# xlr_headphone_amp.net
KiCad netlist of a schematic drawn in EAGLE
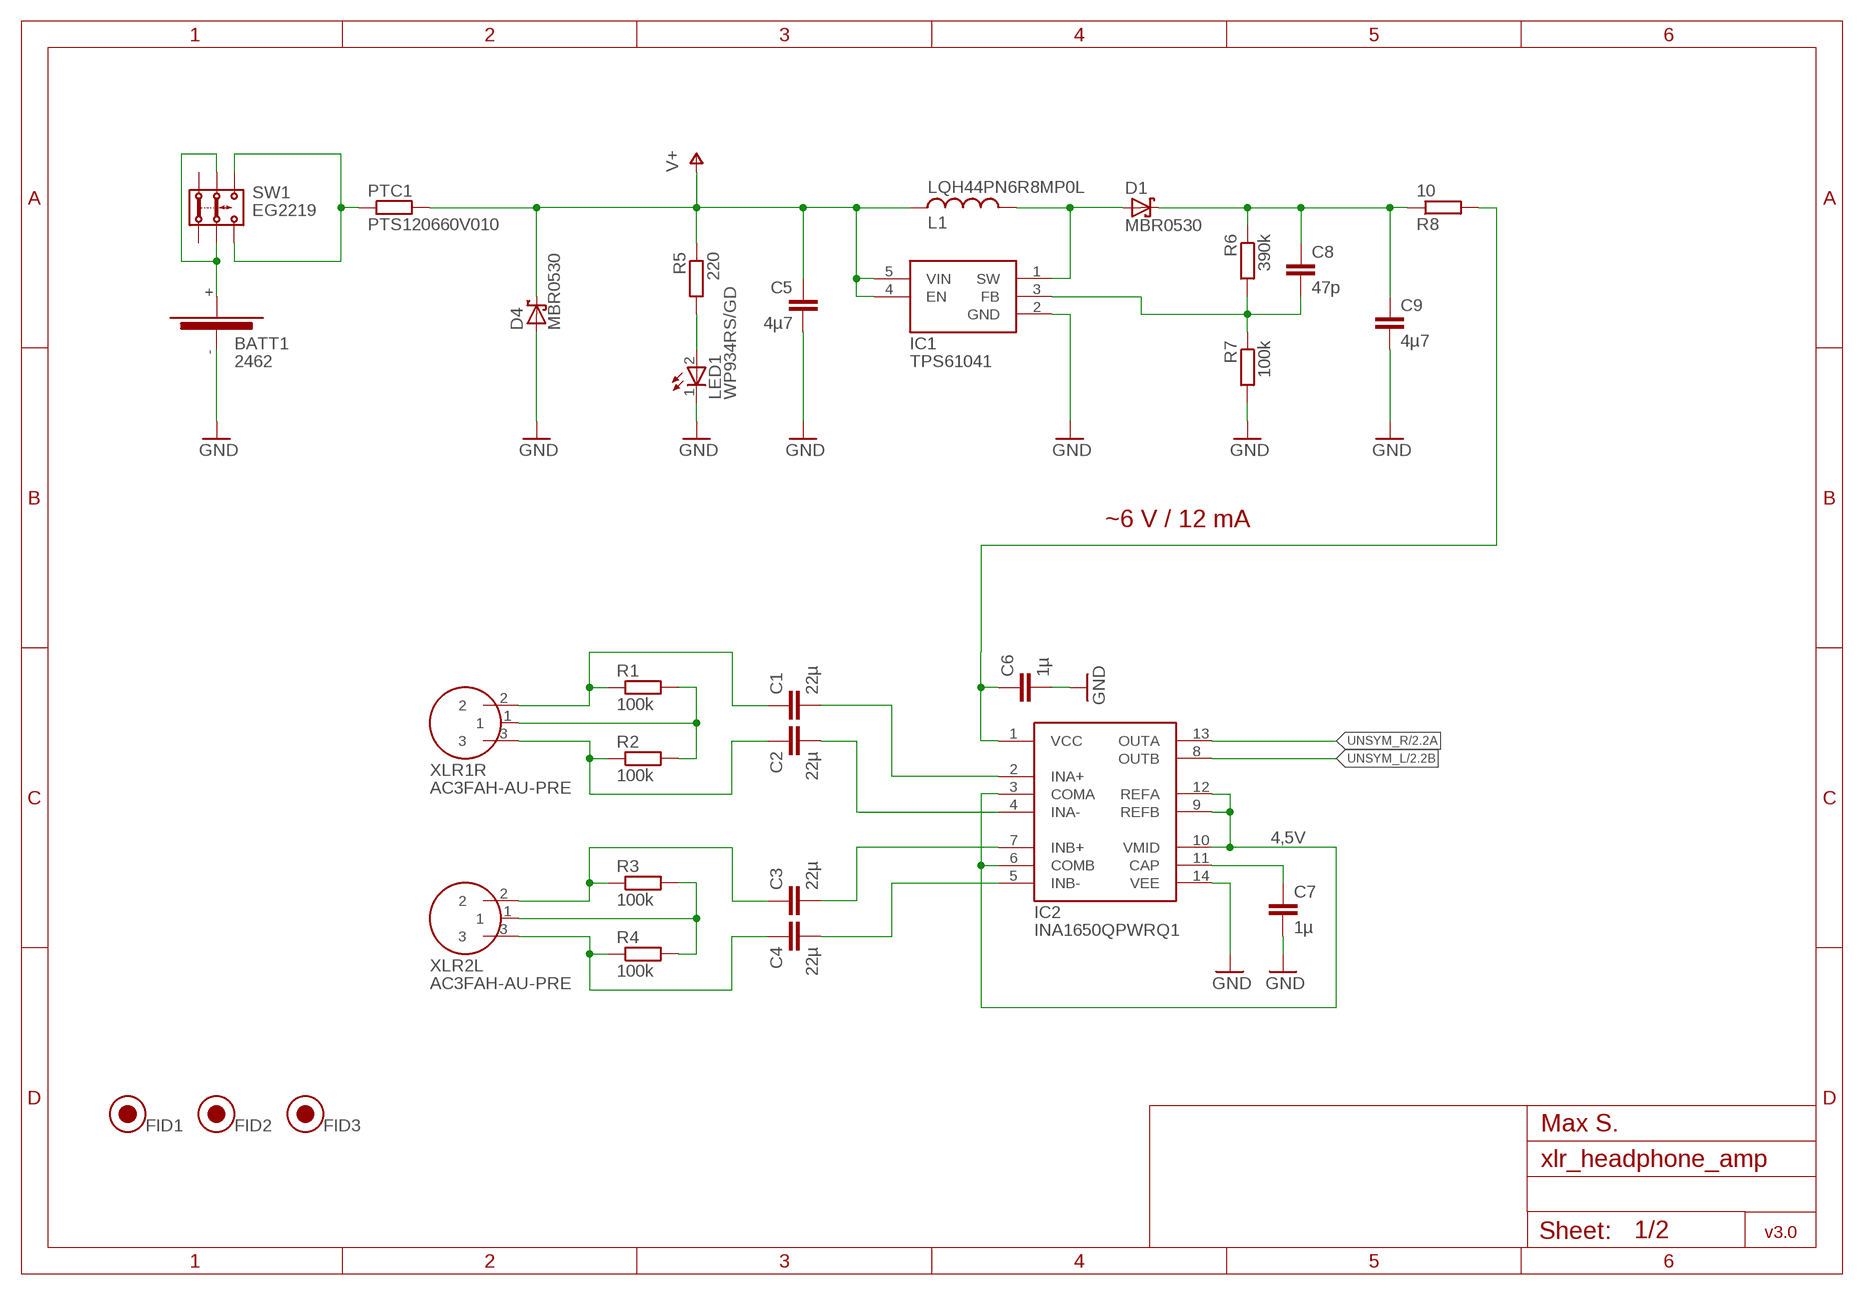
[diagram p0: schematic, sheet 1]
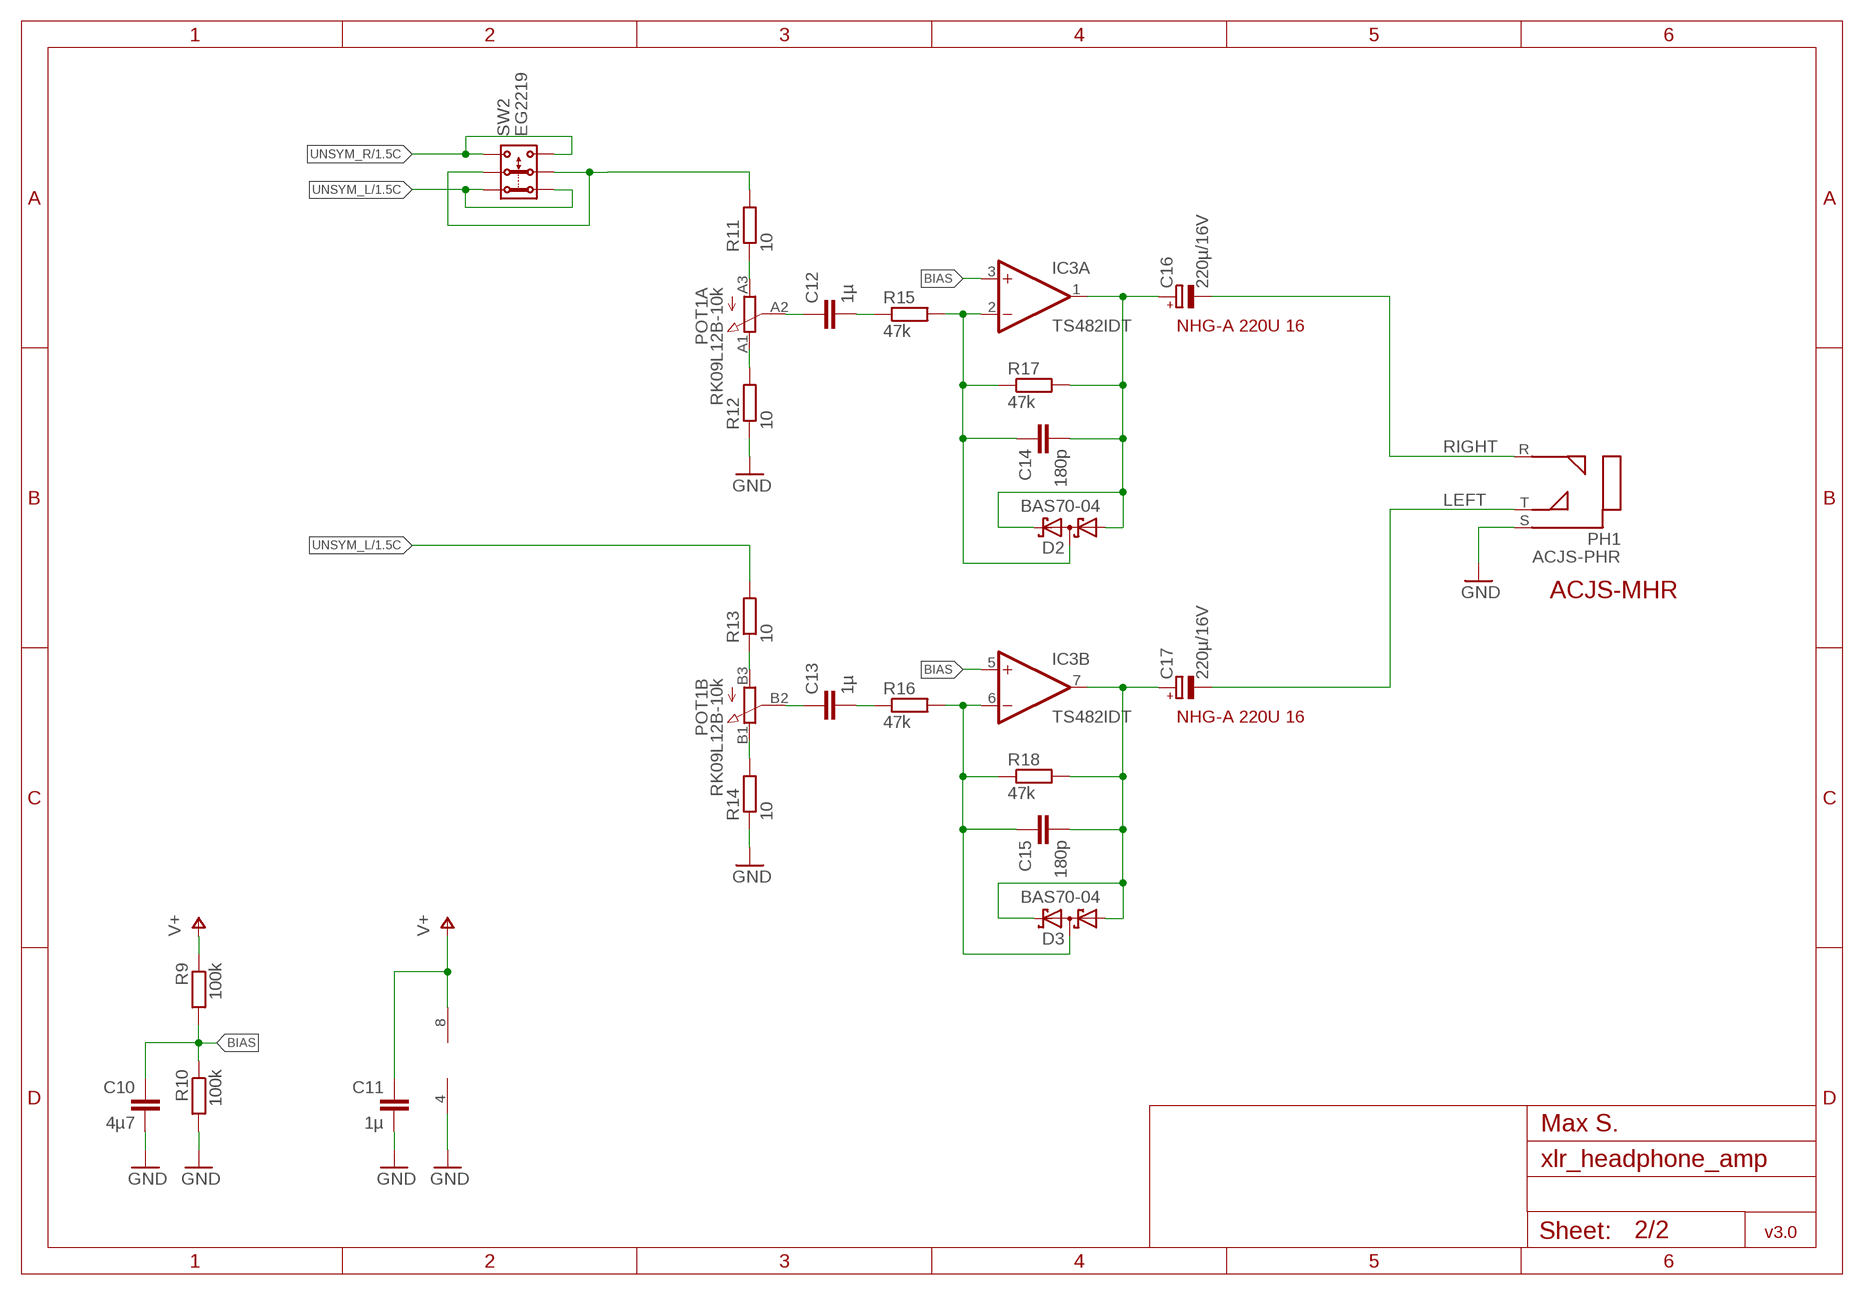
[diagram p1: schematic, sheet 2]

(export (version "E")
  (design (tool "Eeschema 10.0.6"))
  (components
    (comp (ref "BATT1")
      (value "2462")
      (footprint "eagle-import:2462")
      (libsource (lib "eagle-import") (part "BATT_HOLDERBATT"))
    )
    (comp (ref "C1")
      (value "22µ")
      (footprint "eagle-import:C1206")
      (libsource (lib "eagle-import") (part "C_EU1206"))
    )
    (comp (ref "C2")
      (value "22µ")
      (footprint "eagle-import:C1206")
      (libsource (lib "eagle-import") (part "C_EU1206"))
    )
    (comp (ref "C3")
      (value "22µ")
      (footprint "eagle-import:C1206")
      (libsource (lib "eagle-import") (part "C_EU1206"))
    )
    (comp (ref "C4")
      (value "22µ")
      (footprint "eagle-import:C1206")
      (libsource (lib "eagle-import") (part "C_EU1206"))
    )
    (comp (ref "C5")
      (value "4µ7")
      (footprint "eagle-import:C1206")
      (libsource (lib "eagle-import") (part "C_EU1206"))
    )
    (comp (ref "C6")
      (value "1µ")
      (footprint "eagle-import:C1206")
      (libsource (lib "eagle-import") (part "C_EU1206"))
    )
    (comp (ref "C7")
      (value "1µ")
      (footprint "eagle-import:C1206")
      (libsource (lib "eagle-import") (part "C_EU1206"))
    )
    (comp (ref "C8")
      (value "47p")
      (footprint "eagle-import:C1206")
      (libsource (lib "eagle-import") (part "C_EU1206"))
    )
    (comp (ref "C9")
      (value "4µ7")
      (footprint "eagle-import:C1206")
      (libsource (lib "eagle-import") (part "C_EU1206"))
    )
    (comp (ref "D1")
      (value "MBR0530")
      (footprint "eagle-import:SOD123")
      (libsource (lib "eagle-import") (part "SCHOTTKY-DIODESOD123"))
    )
    (comp (ref "D4")
      (value "MBR0530")
      (footprint "eagle-import:SOD123")
      (libsource (lib "eagle-import") (part "SCHOTTKY-DIODESOD123"))
    )
    (comp (ref "FID1")
      (value "FIDICUAL")
      (footprint "eagle-import:FIDICUAL")
      (libsource (lib "eagle-import") (part "FIDICUAL"))
    )
    (comp (ref "FID2")
      (value "FIDICUAL")
      (footprint "eagle-import:FIDICUAL")
      (libsource (lib "eagle-import") (part "FIDICUAL"))
    )
    (comp (ref "FID3")
      (value "FIDICUAL")
      (footprint "eagle-import:FIDICUAL")
      (libsource (lib "eagle-import") (part "FIDICUAL"))
    )
    (comp (ref "IC1")
      (value "TPS61041")
      (footprint "eagle-import:SOT23-5")
      (libsource (lib "eagle-import") (part "TPS6104X"))
    )
    (comp (ref "IC2")
      (value "INA1650QPWRQ1")
      (footprint "eagle-import:R-PDSO-G14")
      (libsource (lib "eagle-import") (part "INA1650INA1650"))
    )
    (comp (ref "L1")
      (value "LQH44PN6R8MP0L")
      (footprint "eagle-import:L1515(4040)")
      (libsource (lib "eagle-import") (part "LL1515"))
    )
    (comp (ref "LED1")
      (value "WP934RS/GD")
      (footprint "eagle-import:WP934")
      (libsource (lib "eagle-import") (part "WP934RS/GD"))
    )
    (comp (ref "PTC1")
      (value "PTS120660V010")
      (footprint "eagle-import:R1206")
      (libsource (lib "eagle-import") (part "R_EUR1206"))
    )
    (comp (ref "R1")
      (value "100k")
      (footprint "eagle-import:R1206")
      (libsource (lib "eagle-import") (part "R_EUR1206"))
    )
    (comp (ref "R2")
      (value "100k")
      (footprint "eagle-import:R1206")
      (libsource (lib "eagle-import") (part "R_EUR1206"))
    )
    (comp (ref "R3")
      (value "100k")
      (footprint "eagle-import:R1206")
      (libsource (lib "eagle-import") (part "R_EUR1206"))
    )
    (comp (ref "R4")
      (value "100k")
      (footprint "eagle-import:R1206")
      (libsource (lib "eagle-import") (part "R_EUR1206"))
    )
    (comp (ref "R5")
      (value "220")
      (footprint "eagle-import:R1206")
      (libsource (lib "eagle-import") (part "R_EUR1206"))
    )
    (comp (ref "R6")
      (value "390k")
      (footprint "eagle-import:R1206")
      (libsource (lib "eagle-import") (part "R_EUR1206"))
    )
    (comp (ref "R7")
      (value "100k")
      (footprint "eagle-import:R1206")
      (libsource (lib "eagle-import") (part "R_EUR1206"))
    )
    (comp (ref "R8")
      (value "10")
      (footprint "eagle-import:R1206")
      (libsource (lib "eagle-import") (part "R_EUR1206"))
    )
    (comp (ref "SW1")
      (value "EG2219")
      (footprint "eagle-import:EG2219")
      (libsource (lib "eagle-import") (part "SW_2P2T"))
    )
    (comp (ref "XLR1R")
      (value "AC3FAH-AU-PRE")
      (footprint "eagle-import:AC3FAH")
      (libsource (lib "eagle-import") (part "XLR_CONNECTORFEMALE"))
    )
    (comp (ref "XLR2L")
      (value "AC3FAH-AU-PRE")
      (footprint "eagle-import:AC3FAH")
      (libsource (lib "eagle-import") (part "XLR_CONNECTORFEMALE"))
    )
    (comp (ref "C10")
      (value "4µ7")
      (footprint "eagle-import:C1206")
      (libsource (lib "eagle-import") (part "C_EU1206"))
    )
    (comp (ref "C11")
      (value "1µ")
      (footprint "eagle-import:C1206")
      (libsource (lib "eagle-import") (part "C_EU1206"))
    )
    (comp (ref "C12")
      (value "1µ")
      (footprint "eagle-import:C1206")
      (libsource (lib "eagle-import") (part "C_EU1206"))
    )
    (comp (ref "C13")
      (value "1µ")
      (footprint "eagle-import:C1206")
      (libsource (lib "eagle-import") (part "C_EU1206"))
    )
    (comp (ref "C14")
      (value "180p")
      (footprint "eagle-import:C1206")
      (libsource (lib "eagle-import") (part "C_EU1206"))
    )
    (comp (ref "C15")
      (value "180p")
      (footprint "eagle-import:C1206")
      (libsource (lib "eagle-import") (part "C_EU1206"))
    )
    (comp (ref "C16")
      (value "220µ/16V")
      (footprint "eagle-import:E2,5-6")
      (libsource (lib "eagle-import") (part "CPOL-EUE2.5-6"))
    )
    (comp (ref "C17")
      (value "220µ/16V")
      (footprint "eagle-import:E2,5-6")
      (libsource (lib "eagle-import") (part "CPOL-EUE2.5-6"))
    )
    (comp (ref "D2")
      (value "BAS70-04")
      (footprint "eagle-import:SOT23")
      (libsource (lib "eagle-import") (part "BAS70-04"))
    )
    (comp (ref "D3")
      (value "BAS70-04")
      (footprint "eagle-import:SOT23")
      (libsource (lib "eagle-import") (part "BAS70-04"))
    )
    (comp (ref "IC3")
      (value "TS482IDT")
      (footprint "eagle-import:SO08")
      (libsource (lib "eagle-import") (part "LM358D"))
    )
    (comp (ref "PH1")
      (value "ACJS-PHR")
      (footprint "eagle-import:ACJS")
      (libsource (lib "eagle-import") (part "1/4{dblquote}_JACK-MH"))
    )
    (comp (ref "POT1")
      (value "RK09L12B-10k")
      (footprint "eagle-import:RK09L12")
      (libsource (lib "eagle-import") (part "AUDIO_POTRK09L12"))
    )
    (comp (ref "R9")
      (value "100k")
      (footprint "eagle-import:R1206")
      (libsource (lib "eagle-import") (part "R_EUR1206"))
    )
    (comp (ref "R10")
      (value "100k")
      (footprint "eagle-import:R1206")
      (libsource (lib "eagle-import") (part "R_EUR1206"))
    )
    (comp (ref "R11")
      (value "10")
      (footprint "eagle-import:R1206")
      (libsource (lib "eagle-import") (part "R_EUR1206"))
    )
    (comp (ref "R12")
      (value "10")
      (footprint "eagle-import:R1206")
      (libsource (lib "eagle-import") (part "R_EUR1206"))
    )
    (comp (ref "R13")
      (value "10")
      (footprint "eagle-import:R1206")
      (libsource (lib "eagle-import") (part "R_EUR1206"))
    )
    (comp (ref "R14")
      (value "10")
      (footprint "eagle-import:R1206")
      (libsource (lib "eagle-import") (part "R_EUR1206"))
    )
    (comp (ref "R15")
      (value "47k")
      (footprint "eagle-import:R1206")
      (libsource (lib "eagle-import") (part "R_EUR1206"))
    )
    (comp (ref "R16")
      (value "47k")
      (footprint "eagle-import:R1206")
      (libsource (lib "eagle-import") (part "R_EUR1206"))
    )
    (comp (ref "R17")
      (value "47k")
      (footprint "eagle-import:R1206")
      (libsource (lib "eagle-import") (part "R_EUR1206"))
    )
    (comp (ref "R18")
      (value "47k")
      (footprint "eagle-import:R1206")
      (libsource (lib "eagle-import") (part "R_EUR1206"))
    )
    (comp (ref "SW2")
      (value "EG2219")
      (footprint "eagle-import:EG2219")
      (libsource (lib "eagle-import") (part "SW_2P2T"))
    )
  )
  (nets
    (net (code "1") (name "4,5V") (class "Default")
      (node (ref "IC2") (pin "10") (pinfunction "VMID_10") (pintype "bidirectional"))
      (node (ref "IC2") (pin "12") (pinfunction "REFA_12") (pintype "bidirectional"))
      (node (ref "IC2") (pin "3") (pinfunction "COMA_3") (pintype "bidirectional"))
      (node (ref "IC2") (pin "6") (pinfunction "COMB_6") (pintype "bidirectional"))
      (node (ref "IC2") (pin "9") (pinfunction "REFB_9") (pintype "bidirectional"))
    )
    (net (code "2") (name "BIAS") (class "Default")
      (node (ref "C10") (pin "1") (pinfunction "1_1") (pintype "passive"))
      (node (ref "IC3") (pin "3") (pinfunction "+IN_3") (pintype "input"))
      (node (ref "IC3") (pin "5") (pinfunction "+IN_5") (pintype "input"))
      (node (ref "R10") (pin "1") (pinfunction "1_1") (pintype "passive"))
      (node (ref "R9") (pin "2") (pinfunction "2_2") (pintype "passive"))
    )
    (net (code "3") (name "GND") (class "Default")
      (node (ref "BATT1") (pin "-") (pinfunction "NEG_-") (pintype "bidirectional"))
      (node (ref "C10") (pin "2") (pinfunction "2_2") (pintype "passive"))
      (node (ref "C11") (pin "2") (pinfunction "2_2") (pintype "passive"))
      (node (ref "C5") (pin "2") (pinfunction "2_2") (pintype "passive"))
      (node (ref "C6") (pin "2") (pinfunction "2_2") (pintype "passive"))
      (node (ref "C7") (pin "2") (pinfunction "2_2") (pintype "passive"))
      (node (ref "C9") (pin "2") (pinfunction "2_2") (pintype "passive"))
      (node (ref "D4") (pin "A") (pinfunction "A_A") (pintype "passive"))
      (node (ref "IC1") (pin "2") (pinfunction "GND_2") (pintype "bidirectional"))
      (node (ref "IC2") (pin "14") (pinfunction "VEE_14") (pintype "bidirectional"))
      (node (ref "IC3") (pin "4") (pinfunction "V-_4") (pintype "power_in"))
      (node (ref "LED1") (pin "1") (pinfunction "C_1") (pintype "passive"))
      (node (ref "PH1") (pin "S") (pinfunction "S_S") (pintype "bidirectional"))
      (node (ref "R10") (pin "2") (pinfunction "2_2") (pintype "passive"))
      (node (ref "R12") (pin "1") (pinfunction "1_1") (pintype "passive"))
      (node (ref "R14") (pin "1") (pinfunction "1_1") (pintype "passive"))
      (node (ref "R7") (pin "2") (pinfunction "2_2") (pintype "passive"))
    )
    (net (code "4") (name "LEFT") (class "Default")
      (node (ref "C17") (pin "-") (pinfunction "-_-") (pintype "passive"))
      (node (ref "PH1") (pin "T") (pinfunction "T_T") (pintype "bidirectional"))
    )
    (net (code "5") (name "Net-(BATT1-POS)") (class "Default")
      (node (ref "BATT1") (pin "+") (pinfunction "POS_+") (pintype "bidirectional"))
      (node (ref "SW1") (pin "B1") (pinfunction "B1_B1") (pintype "passive"))
      (node (ref "SW1") (pin "B2") (pinfunction "B2_B2") (pintype "passive"))
    )
    (net (code "6") (name "Net-(C1-Pad1)") (class "Default")
      (node (ref "C1") (pin "1") (pinfunction "1_1") (pintype "passive"))
      (node (ref "R1") (pin "1") (pinfunction "1_1") (pintype "passive"))
      (node (ref "XLR1R") (pin "2") (pinfunction "2_2") (pintype "bidirectional"))
    )
    (net (code "7") (name "Net-(C2-Pad1)") (class "Default")
      (node (ref "C2") (pin "1") (pinfunction "1_1") (pintype "passive"))
      (node (ref "R2") (pin "1") (pinfunction "1_1") (pintype "passive"))
      (node (ref "XLR1R") (pin "3") (pinfunction "3_3") (pintype "bidirectional"))
    )
    (net (code "8") (name "Net-(C3-Pad1)") (class "Default")
      (node (ref "C3") (pin "1") (pinfunction "1_1") (pintype "passive"))
      (node (ref "R3") (pin "1") (pinfunction "1_1") (pintype "passive"))
      (node (ref "XLR2L") (pin "2") (pinfunction "2_2") (pintype "bidirectional"))
    )
    (net (code "9") (name "Net-(C4-Pad1)") (class "Default")
      (node (ref "C4") (pin "1") (pinfunction "1_1") (pintype "passive"))
      (node (ref "R4") (pin "1") (pinfunction "1_1") (pintype "passive"))
      (node (ref "XLR2L") (pin "3") (pinfunction "3_3") (pintype "bidirectional"))
    )
    (net (code "10") (name "Net-(C8-Pad1)") (class "Default")
      (node (ref "C8") (pin "1") (pinfunction "1_1") (pintype "passive"))
      (node (ref "C9") (pin "1") (pinfunction "1_1") (pintype "passive"))
      (node (ref "D1") (pin "C") (pinfunction "C_C") (pintype "passive"))
      (node (ref "R6") (pin "1") (pinfunction "1_1") (pintype "passive"))
      (node (ref "R8") (pin "1") (pinfunction "1_1") (pintype "passive"))
    )
    (net (code "11") (name "Net-(C12-Pad2)") (class "Default")
      (node (ref "C12") (pin "2") (pinfunction "2_2") (pintype "passive"))
      (node (ref "R15") (pin "1") (pinfunction "1_1") (pintype "passive"))
    )
    (net (code "12") (name "Net-(C13-Pad2)") (class "Default")
      (node (ref "C13") (pin "2") (pinfunction "2_2") (pintype "passive"))
      (node (ref "R16") (pin "1") (pinfunction "1_1") (pintype "passive"))
    )
    (net (code "13") (name "Net-(D2-A1)") (class "Default")
      (node (ref "C14") (pin "2") (pinfunction "2_2") (pintype "passive"))
      (node (ref "C16") (pin "+") (pinfunction "+_+") (pintype "passive"))
      (node (ref "D2") (pin "1") (pinfunction "A1_1") (pintype "passive"))
      (node (ref "D2") (pin "2") (pinfunction "C2_2") (pintype "passive"))
      (node (ref "IC3") (pin "1") (pinfunction "OUT_1") (pintype "output"))
      (node (ref "R17") (pin "2") (pinfunction "2_2") (pintype "passive"))
    )
    (net (code "14") (name "Net-(D2-C1A2)") (class "Default")
      (node (ref "C14") (pin "1") (pinfunction "1_1") (pintype "passive"))
      (node (ref "D2") (pin "3") (pinfunction "C1A2_3") (pintype "passive"))
      (node (ref "IC3") (pin "2") (pinfunction "-IN_2") (pintype "input"))
      (node (ref "R15") (pin "2") (pinfunction "2_2") (pintype "passive"))
      (node (ref "R17") (pin "1") (pinfunction "1_1") (pintype "passive"))
    )
    (net (code "15") (name "Net-(D3-A1)") (class "Default")
      (node (ref "C15") (pin "2") (pinfunction "2_2") (pintype "passive"))
      (node (ref "C17") (pin "+") (pinfunction "+_+") (pintype "passive"))
      (node (ref "D3") (pin "1") (pinfunction "A1_1") (pintype "passive"))
      (node (ref "D3") (pin "2") (pinfunction "C2_2") (pintype "passive"))
      (node (ref "IC3") (pin "7") (pinfunction "OUT_7") (pintype "output"))
      (node (ref "R18") (pin "2") (pinfunction "2_2") (pintype "passive"))
    )
    (net (code "16") (name "Net-(D3-C1A2)") (class "Default")
      (node (ref "C15") (pin "1") (pinfunction "1_1") (pintype "passive"))
      (node (ref "D3") (pin "3") (pinfunction "C1A2_3") (pintype "passive"))
      (node (ref "IC3") (pin "6") (pinfunction "-IN_6") (pintype "input"))
      (node (ref "R16") (pin "2") (pinfunction "2_2") (pintype "passive"))
      (node (ref "R18") (pin "1") (pinfunction "1_1") (pintype "passive"))
    )
    (net (code "17") (name "Net-(IC1-FB)") (class "Default")
      (node (ref "C8") (pin "2") (pinfunction "2_2") (pintype "passive"))
      (node (ref "IC1") (pin "3") (pinfunction "FB_3") (pintype "bidirectional"))
      (node (ref "R6") (pin "2") (pinfunction "2_2") (pintype "passive"))
      (node (ref "R7") (pin "1") (pinfunction "1_1") (pintype "passive"))
    )
    (net (code "18") (name "Net-(IC1-SW)") (class "Default")
      (node (ref "D1") (pin "A") (pinfunction "A_A") (pintype "passive"))
      (node (ref "IC1") (pin "1") (pinfunction "SW_1") (pintype "bidirectional"))
      (node (ref "L1") (pin "1") (pinfunction "1_1") (pintype "passive"))
    )
    (net (code "19") (name "Net-(IC2-CAP)") (class "Default")
      (node (ref "C7") (pin "1") (pinfunction "1_1") (pintype "passive"))
      (node (ref "IC2") (pin "11") (pinfunction "CAP_11") (pintype "bidirectional"))
    )
    (net (code "20") (name "Net-(IC2-INA+)") (class "Default")
      (node (ref "C1") (pin "2") (pinfunction "2_2") (pintype "passive"))
      (node (ref "IC2") (pin "2") (pinfunction "INA+_2") (pintype "bidirectional"))
    )
    (net (code "21") (name "Net-(IC2-INA-)") (class "Default")
      (node (ref "C2") (pin "2") (pinfunction "2_2") (pintype "passive"))
      (node (ref "IC2") (pin "4") (pinfunction "INA-_4") (pintype "bidirectional"))
    )
    (net (code "22") (name "Net-(IC2-INB+)") (class "Default")
      (node (ref "C3") (pin "2") (pinfunction "2_2") (pintype "passive"))
      (node (ref "IC2") (pin "7") (pinfunction "INB+_7") (pintype "bidirectional"))
    )
    (net (code "23") (name "Net-(IC2-INB-)") (class "Default")
      (node (ref "C4") (pin "2") (pinfunction "2_2") (pintype "passive"))
      (node (ref "IC2") (pin "5") (pinfunction "INB-_5") (pintype "bidirectional"))
    )
    (net (code "24") (name "Net-(IC2-VCC)") (class "Default")
      (node (ref "C6") (pin "1") (pinfunction "1_1") (pintype "passive"))
      (node (ref "IC2") (pin "1") (pinfunction "VCC_1") (pintype "bidirectional"))
      (node (ref "R8") (pin "2") (pinfunction "2_2") (pintype "passive"))
    )
    (net (code "25") (name "Net-(LED1-A)") (class "Default")
      (node (ref "LED1") (pin "2") (pinfunction "A_2") (pintype "passive"))
      (node (ref "R5") (pin "2") (pinfunction "2_2") (pintype "passive"))
    )
    (net (code "26") (name "Net-(POT1A-1)") (class "Default")
      (node (ref "POT1") (pin "A1") (pinfunction "1_A1") (pintype "passive"))
      (node (ref "R12") (pin "2") (pinfunction "2_2") (pintype "passive"))
    )
    (net (code "27") (name "Net-(POT1A-2)") (class "Default")
      (node (ref "C12") (pin "1") (pinfunction "1_1") (pintype "passive"))
      (node (ref "POT1") (pin "A2") (pinfunction "2_A2") (pintype "passive"))
    )
    (net (code "28") (name "Net-(POT1A-3)") (class "Default")
      (node (ref "POT1") (pin "A3") (pinfunction "3_A3") (pintype "passive"))
      (node (ref "R11") (pin "1") (pinfunction "1_1") (pintype "passive"))
    )
    (net (code "29") (name "Net-(POT1B-1)") (class "Default")
      (node (ref "POT1") (pin "B1") (pinfunction "1_B1") (pintype "passive"))
      (node (ref "R14") (pin "2") (pinfunction "2_2") (pintype "passive"))
    )
    (net (code "30") (name "Net-(POT1B-2)") (class "Default")
      (node (ref "C13") (pin "1") (pinfunction "1_1") (pintype "passive"))
      (node (ref "POT1") (pin "B2") (pinfunction "2_B2") (pintype "passive"))
    )
    (net (code "31") (name "Net-(POT1B-3)") (class "Default")
      (node (ref "POT1") (pin "B3") (pinfunction "3_B3") (pintype "passive"))
      (node (ref "R13") (pin "1") (pinfunction "1_1") (pintype "passive"))
    )
    (net (code "32") (name "Net-(PTC1-Pad1)") (class "Default")
      (node (ref "PTC1") (pin "1") (pinfunction "1_1") (pintype "passive"))
      (node (ref "SW1") (pin "C1") (pinfunction "C1_C1") (pintype "passive"))
      (node (ref "SW1") (pin "C2") (pinfunction "C2_C2") (pintype "passive"))
    )
    (net (code "33") (name "Net-(R1-Pad2)") (class "Default")
      (node (ref "R1") (pin "2") (pinfunction "2_2") (pintype "passive"))
      (node (ref "R2") (pin "2") (pinfunction "2_2") (pintype "passive"))
      (node (ref "XLR1R") (pin "1") (pinfunction "1_1") (pintype "bidirectional"))
    )
    (net (code "34") (name "Net-(R3-Pad2)") (class "Default")
      (node (ref "R3") (pin "2") (pinfunction "2_2") (pintype "passive"))
      (node (ref "R4") (pin "2") (pinfunction "2_2") (pintype "passive"))
      (node (ref "XLR2L") (pin "1") (pinfunction "1_1") (pintype "bidirectional"))
    )
    (net (code "35") (name "Net-(R11-Pad2)") (class "Default")
      (node (ref "R11") (pin "2") (pinfunction "2_2") (pintype "passive"))
      (node (ref "SW2") (pin "B1") (pinfunction "B1_B1") (pintype "passive"))
      (node (ref "SW2") (pin "B2") (pinfunction "B2_B2") (pintype "passive"))
    )
    (net (code "36") (name "RIGHT") (class "Default")
      (node (ref "C16") (pin "-") (pinfunction "-_-") (pintype "passive"))
      (node (ref "PH1") (pin "R") (pinfunction "R_R") (pintype "bidirectional"))
    )
    (net (code "37") (name "UNSYM_L") (class "Default")
      (node (ref "IC2") (pin "8") (pinfunction "OUTB_8") (pintype "bidirectional"))
      (node (ref "R13") (pin "2") (pinfunction "2_2") (pintype "passive"))
      (node (ref "SW2") (pin "A1") (pinfunction "A1_A1") (pintype "passive"))
      (node (ref "SW2") (pin "A2") (pinfunction "A2_A2") (pintype "passive"))
    )
    (net (code "38") (name "UNSYM_R") (class "Default")
      (node (ref "IC2") (pin "13") (pinfunction "OUTA_13") (pintype "bidirectional"))
      (node (ref "SW2") (pin "C1") (pinfunction "C1_C1") (pintype "passive"))
      (node (ref "SW2") (pin "C2") (pinfunction "C2_C2") (pintype "passive"))
    )
    (net (code "39") (name "V+") (class "Default")
      (node (ref "C11") (pin "1") (pinfunction "1_1") (pintype "passive"))
      (node (ref "C5") (pin "1") (pinfunction "1_1") (pintype "passive"))
      (node (ref "D4") (pin "C") (pinfunction "C_C") (pintype "passive"))
      (node (ref "IC1") (pin "4") (pinfunction "EN_4") (pintype "bidirectional"))
      (node (ref "IC1") (pin "5") (pinfunction "VIN_5") (pintype "bidirectional"))
      (node (ref "IC3") (pin "8") (pinfunction "V+_8") (pintype "power_in"))
      (node (ref "L1") (pin "2") (pinfunction "2_2") (pintype "passive"))
      (node (ref "PTC1") (pin "2") (pinfunction "2_2") (pintype "passive"))
      (node (ref "R5") (pin "1") (pinfunction "1_1") (pintype "passive"))
      (node (ref "R9") (pin "1") (pinfunction "1_1") (pintype "passive"))
    )
    (net (code "40") (name "unconnected-(SW1-PadA1)") (class "Default")
      (node (ref "SW1") (pin "A1") (pinfunction "A1_A1") (pintype "passive"))
    )
    (net (code "41") (name "unconnected-(SW1-PadA2)") (class "Default")
      (node (ref "SW1") (pin "A2") (pinfunction "A2_A2") (pintype "passive"))
    )
  )
)
